# PowerGroup.net
KiCad netlist of a schematic drawn in Altium Designer
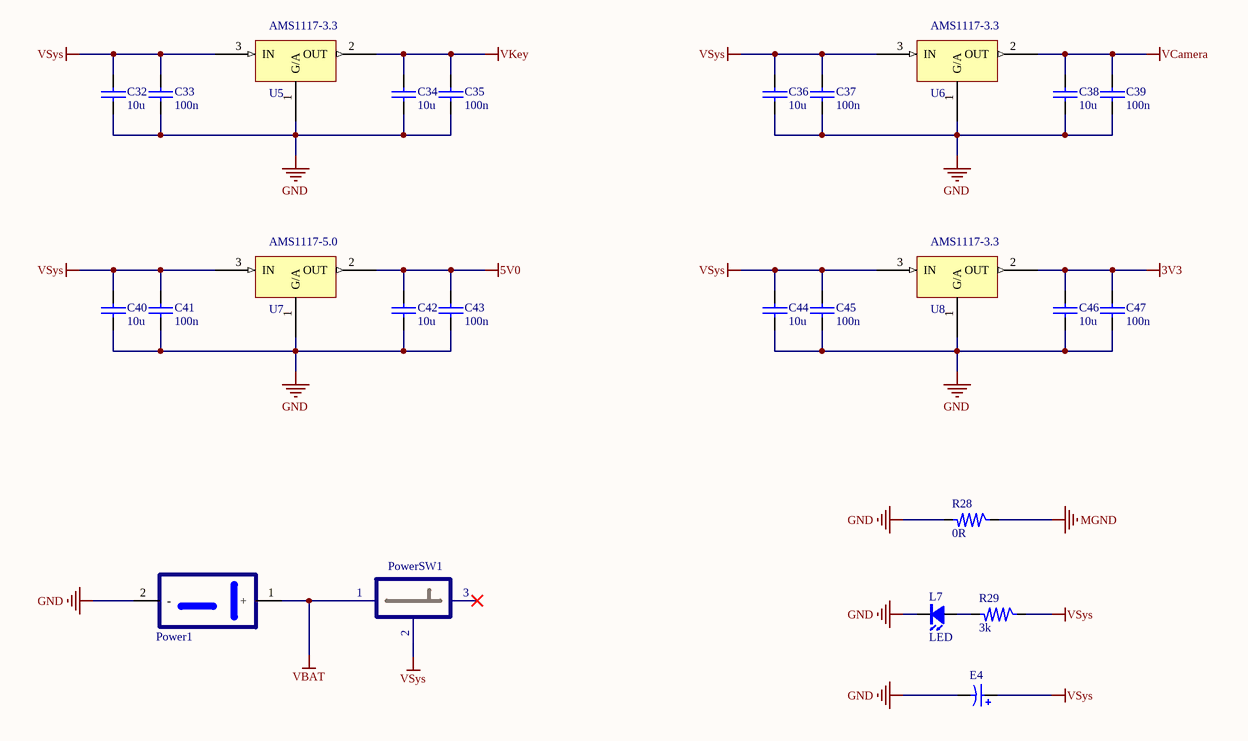
[diagram p0: PowerGroup.SchDoc]

(export (version "E")
  (design (tool "Eeschema 10.0.6"))
  (components
    (comp (ref "C32")
      (value "10u")
      (footprint "C0805")
      (description "电容")
      (libsource (lib "LQ_Integrated_Library") (part "Capacitor"))
    )
    (comp (ref "C33")
      (value "100n")
      (footprint "C0603")
      (description "电容")
      (libsource (lib "LQ_Integrated_Library") (part "Capacitor"))
    )
    (comp (ref "C34")
      (value "10u")
      (footprint "C0805")
      (description "电容")
      (libsource (lib "LQ_Integrated_Library") (part "Capacitor"))
    )
    (comp (ref "C35")
      (value "100n")
      (footprint "C0603")
      (description "电容")
      (libsource (lib "LQ_Integrated_Library") (part "Capacitor"))
    )
    (comp (ref "C36")
      (value "10u")
      (footprint "C0805")
      (description "电容")
      (libsource (lib "LQ_Integrated_Library") (part "Capacitor"))
    )
    (comp (ref "C37")
      (value "100n")
      (footprint "C0603")
      (description "电容")
      (libsource (lib "LQ_Integrated_Library") (part "Capacitor"))
    )
    (comp (ref "C38")
      (value "10u")
      (footprint "C0805")
      (description "电容")
      (libsource (lib "LQ_Integrated_Library") (part "Capacitor"))
    )
    (comp (ref "C39")
      (value "100n")
      (footprint "C0603")
      (description "电容")
      (libsource (lib "LQ_Integrated_Library") (part "Capacitor"))
    )
    (comp (ref "C40")
      (value "10u")
      (footprint "C0805")
      (description "电容")
      (libsource (lib "LQ_Integrated_Library") (part "Capacitor"))
    )
    (comp (ref "C41")
      (value "100n")
      (footprint "C0603")
      (description "电容")
      (libsource (lib "LQ_Integrated_Library") (part "Capacitor"))
    )
    (comp (ref "C42")
      (value "10u")
      (footprint "C0805")
      (description "电容")
      (libsource (lib "LQ_Integrated_Library") (part "Capacitor"))
    )
    (comp (ref "C43")
      (value "100n")
      (footprint "C0603")
      (description "电容")
      (libsource (lib "LQ_Integrated_Library") (part "Capacitor"))
    )
    (comp (ref "C44")
      (value "10u")
      (footprint "C0805")
      (description "电容")
      (libsource (lib "LQ_Integrated_Library") (part "Capacitor"))
    )
    (comp (ref "C45")
      (value "100n")
      (footprint "C0603")
      (description "电容")
      (libsource (lib "LQ_Integrated_Library") (part "Capacitor"))
    )
    (comp (ref "C46")
      (value "10u")
      (footprint "C0805")
      (description "电容")
      (libsource (lib "LQ_Integrated_Library") (part "Capacitor"))
    )
    (comp (ref "C47")
      (value "100n")
      (footprint "C0603")
      (description "电容")
      (libsource (lib "LQ_Integrated_Library") (part "Capacitor"))
    )
    (comp (ref "E4")
      (value "Capacitor-Polarity")
      (footprint "CAP-E SMD-D")
      (description "极性电容")
      (libsource (lib "LQ_Integrated_Library") (part "Capacitor-Polarity"))
    )
    (comp (ref "L7")
      (value "LED")
      (footprint "LED0805TB")
      (libsource (lib "LQ_Integrated_Library") (part "LED"))
    )
    (comp (ref "Power1") (value "XT60") (footprint "T型头") (libsource (lib "ZZCDevice") (part "XT60")))
    (comp (ref "PowerSW1")
      (value "Power")
      (footprint "NIUZI_SWITCH")
      (libsource (lib "ZZCDevice") (part "PowerSW"))
    )
    (comp (ref "R28")
      (value "0R")
      (footprint "R0603")
      (description "电阻")
      (libsource (lib "LQ_Integrated_Library") (part "Resistor"))
    )
    (comp (ref "R29")
      (value "3k")
      (footprint "R0603")
      (description "电阻")
      (libsource (lib "LQ_Integrated_Library") (part "Resistor"))
    )
    (comp (ref "U5")
      (value "AMS1117-3.3")
      (footprint "SOT223")
      (description "稳压芯片")
      (libsource (lib "LQ_Integrated_Library") (part "AMS1117-XX"))
    )
    (comp (ref "U6")
      (value "AMS1117-3.3")
      (footprint "SOT223")
      (description "稳压芯片")
      (libsource (lib "LQ_Integrated_Library") (part "AMS1117-XX"))
    )
    (comp (ref "U7")
      (value "AMS1117-5.0")
      (footprint "SOT223")
      (description "稳压芯片")
      (libsource (lib "LQ_Integrated_Library") (part "AMS1117-XX"))
    )
    (comp (ref "U8")
      (value "AMS1117-3.3")
      (footprint "SOT223")
      (description "稳压芯片")
      (libsource (lib "LQ_Integrated_Library") (part "AMS1117-XX"))
    )
  )
  (nets
    (net (code "1") (name "3V3") (class "Default")
      (node (ref "C46") (pin "1") (pinfunction "1_1") (pintype "passive"))
      (node (ref "C47") (pin "1") (pinfunction "1_1") (pintype "passive"))
      (node (ref "U8") (pin "2") (pinfunction "OUT_2") (pintype "output"))
    )
    (net (code "2") (name "5V0") (class "Default")
      (node (ref "C42") (pin "1") (pinfunction "1_1") (pintype "passive"))
      (node (ref "C43") (pin "1") (pinfunction "1_1") (pintype "passive"))
      (node (ref "U7") (pin "2") (pinfunction "OUT_2") (pintype "output"))
    )
    (net (code "3") (name "GND") (class "Default")
      (node (ref "C32") (pin "2") (pinfunction "2_2") (pintype "passive"))
      (node (ref "C33") (pin "2") (pinfunction "2_2") (pintype "passive"))
      (node (ref "C34") (pin "2") (pinfunction "2_2") (pintype "passive"))
      (node (ref "C35") (pin "2") (pinfunction "2_2") (pintype "passive"))
      (node (ref "C36") (pin "2") (pinfunction "2_2") (pintype "passive"))
      (node (ref "C37") (pin "2") (pinfunction "2_2") (pintype "passive"))
      (node (ref "C38") (pin "2") (pinfunction "2_2") (pintype "passive"))
      (node (ref "C39") (pin "2") (pinfunction "2_2") (pintype "passive"))
      (node (ref "C40") (pin "2") (pinfunction "2_2") (pintype "passive"))
      (node (ref "C41") (pin "2") (pinfunction "2_2") (pintype "passive"))
      (node (ref "C42") (pin "2") (pinfunction "2_2") (pintype "passive"))
      (node (ref "C43") (pin "2") (pinfunction "2_2") (pintype "passive"))
      (node (ref "C44") (pin "2") (pinfunction "2_2") (pintype "passive"))
      (node (ref "C45") (pin "2") (pinfunction "2_2") (pintype "passive"))
      (node (ref "C46") (pin "2") (pinfunction "2_2") (pintype "passive"))
      (node (ref "C47") (pin "2") (pinfunction "2_2") (pintype "passive"))
      (node (ref "E4") (pin "2") (pinfunction "2_2") (pintype "passive"))
      (node (ref "L7") (pin "2") (pinfunction "K_2") (pintype "passive"))
      (node (ref "Power1") (pin "2") (pinfunction "-_2") (pintype "passive"))
      (node (ref "R28") (pin "1") (pinfunction "1_1") (pintype "passive"))
      (node (ref "U5") (pin "1") (pinfunction "G/A_1") (pintype "passive"))
      (node (ref "U6") (pin "1") (pinfunction "G/A_1") (pintype "passive"))
      (node (ref "U7") (pin "1") (pinfunction "G/A_1") (pintype "passive"))
      (node (ref "U8") (pin "1") (pinfunction "G/A_1") (pintype "passive"))
    )
    (net (code "4") (name "MGND") (class "Default")
      (node (ref "R28") (pin "2") (pinfunction "2_2") (pintype "passive"))
    )
    (net (code "5") (name "Net-(L7-A)") (class "Default")
      (node (ref "L7") (pin "1") (pinfunction "A_1") (pintype "passive"))
      (node (ref "R29") (pin "1") (pinfunction "1_1") (pintype "passive"))
    )
    (net (code "6") (name "VBAT") (class "Default")
      (node (ref "Power1") (pin "1") (pinfunction "+_1") (pintype "passive"))
      (node (ref "PowerSW1") (pin "1") (pinfunction "1_1") (pintype "passive"))
    )
    (net (code "7") (name "VCamera") (class "Default")
      (node (ref "C38") (pin "1") (pinfunction "1_1") (pintype "passive"))
      (node (ref "C39") (pin "1") (pinfunction "1_1") (pintype "passive"))
      (node (ref "U6") (pin "2") (pinfunction "OUT_2") (pintype "output"))
    )
    (net (code "8") (name "VKey") (class "Default")
      (node (ref "C34") (pin "1") (pinfunction "1_1") (pintype "passive"))
      (node (ref "C35") (pin "1") (pinfunction "1_1") (pintype "passive"))
      (node (ref "U5") (pin "2") (pinfunction "OUT_2") (pintype "output"))
    )
    (net (code "9") (name "VSys") (class "Default")
      (node (ref "C32") (pin "1") (pinfunction "1_1") (pintype "passive"))
      (node (ref "C33") (pin "1") (pinfunction "1_1") (pintype "passive"))
      (node (ref "C36") (pin "1") (pinfunction "1_1") (pintype "passive"))
      (node (ref "C37") (pin "1") (pinfunction "1_1") (pintype "passive"))
      (node (ref "C40") (pin "1") (pinfunction "1_1") (pintype "passive"))
      (node (ref "C41") (pin "1") (pinfunction "1_1") (pintype "passive"))
      (node (ref "C44") (pin "1") (pinfunction "1_1") (pintype "passive"))
      (node (ref "C45") (pin "1") (pinfunction "1_1") (pintype "passive"))
      (node (ref "E4") (pin "1") (pinfunction "1_1") (pintype "passive"))
      (node (ref "PowerSW1") (pin "2") (pinfunction "2_2") (pintype "passive"))
      (node (ref "R29") (pin "2") (pinfunction "2_2") (pintype "passive"))
      (node (ref "U5") (pin "3") (pinfunction "IN_3") (pintype "input"))
      (node (ref "U6") (pin "3") (pinfunction "IN_3") (pintype "input"))
      (node (ref "U7") (pin "3") (pinfunction "IN_3") (pintype "input"))
      (node (ref "U8") (pin "3") (pinfunction "IN_3") (pintype "input"))
    )
    (net (code "10") (name "unconnected-(PowerSW1-Pad3)") (class "Default")
      (node (ref "PowerSW1") (pin "3") (pinfunction "3_3") (pintype "passive+no_connect"))
    )
  )
)
